# W005.net
KiCad netlist of a schematic drawn in EAGLE
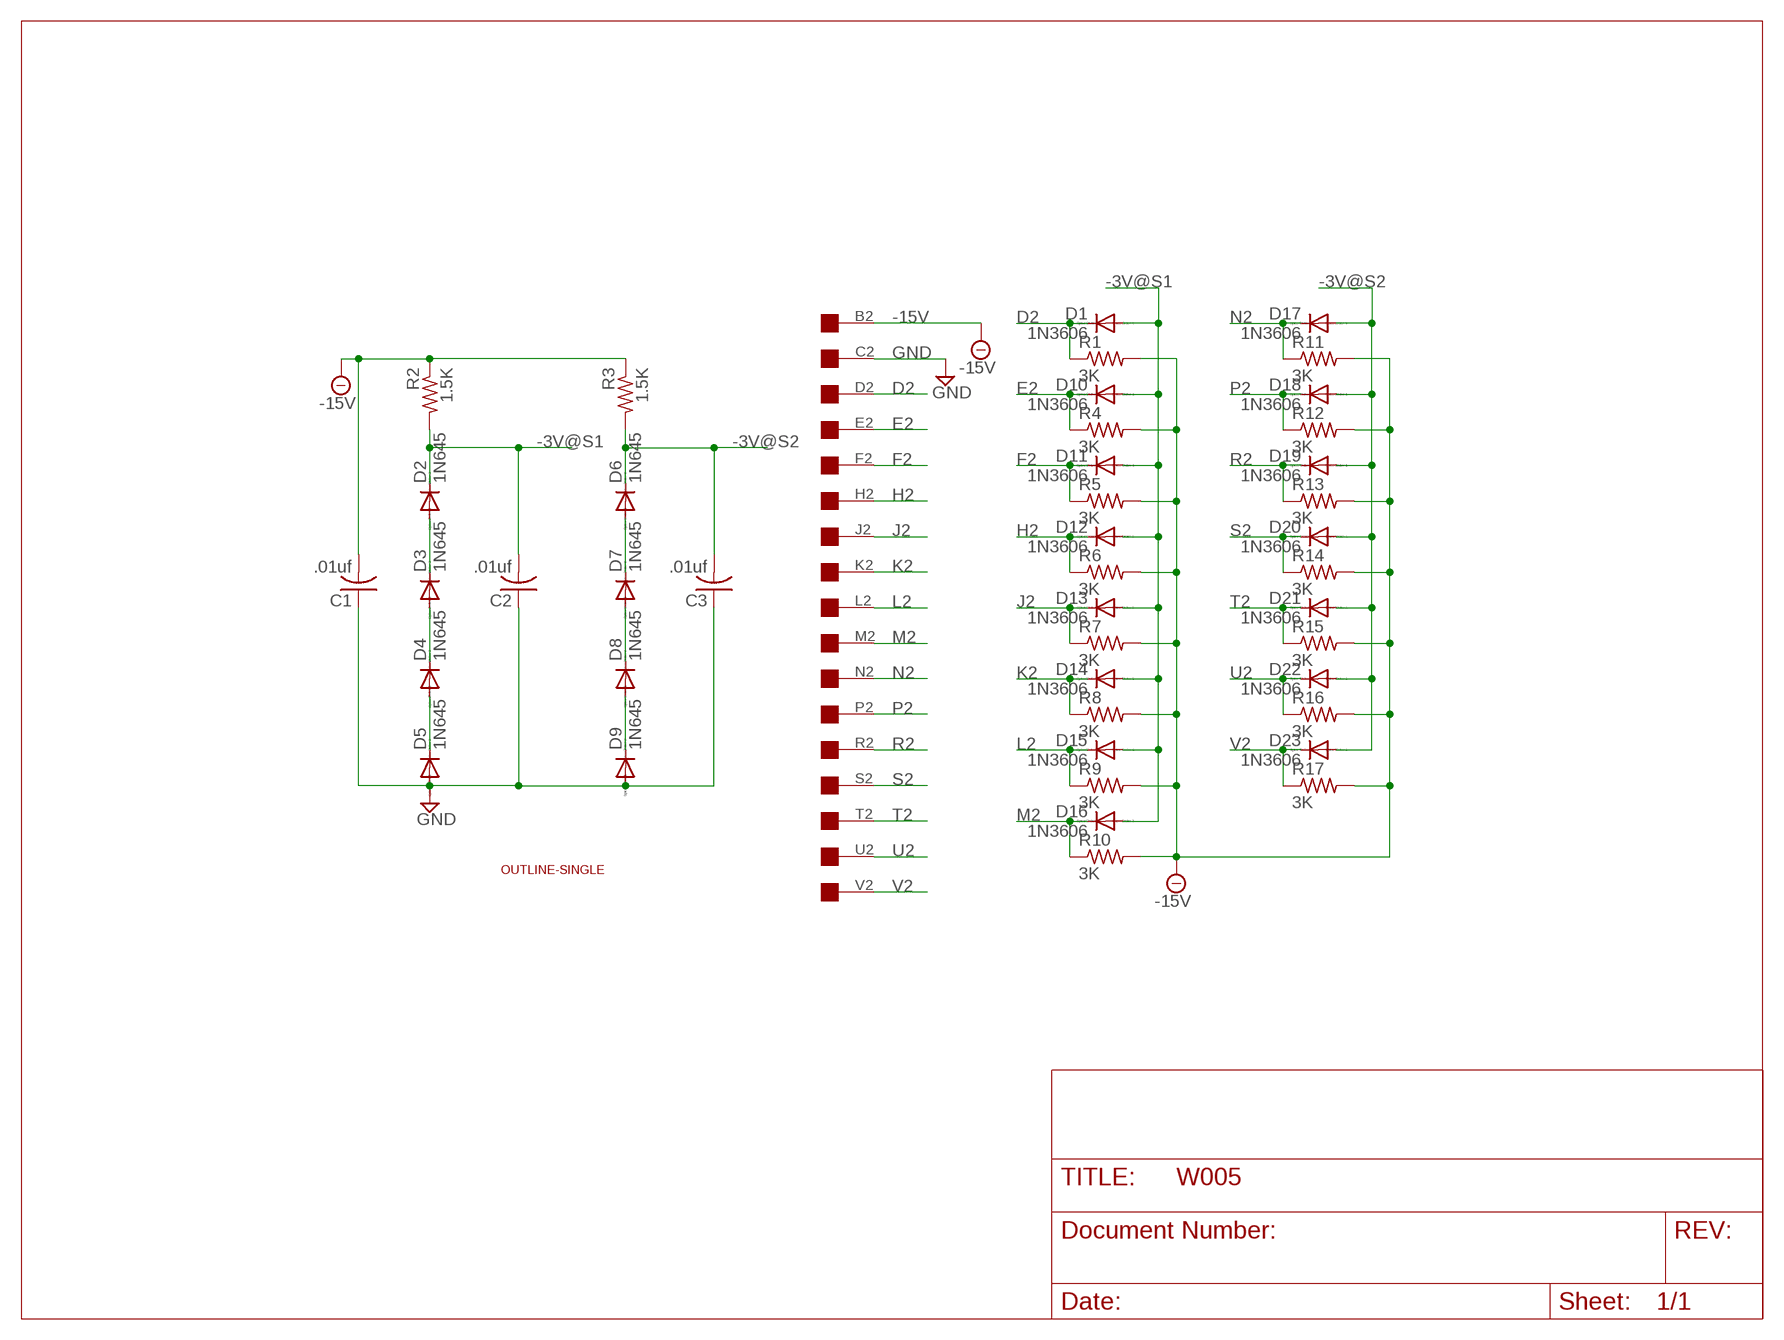
[diagram p0: schematic, sheet 1]

(export (version "E")
  (design (tool "Eeschema 10.0.6"))
  (components
    (comp (ref "C1")
      (value ".01uf")
      (footprint "eagle-import:C050-025X075")
      (libsource (lib "eagle-import") (part "C-US050-025X075"))
    )
    (comp (ref "C2")
      (value ".01uf")
      (footprint "eagle-import:C050-025X075")
      (libsource (lib "eagle-import") (part "C-US050-025X075"))
    )
    (comp (ref "C3")
      (value ".01uf")
      (footprint "eagle-import:C050-025X075")
      (libsource (lib "eagle-import") (part "C-US050-025X075"))
    )
    (comp (ref "D1")
      (value "1N3606")
      (footprint "eagle-import:DO35-10")
      (libsource (lib "eagle-import") (part "1N4148DO35-10"))
    )
    (comp (ref "D2")
      (value "1N645")
      (footprint "eagle-import:DO35-10")
      (libsource (lib "eagle-import") (part "1N4148DO35-10"))
    )
    (comp (ref "D3")
      (value "1N645")
      (footprint "eagle-import:DO35-10")
      (libsource (lib "eagle-import") (part "1N4148DO35-10"))
    )
    (comp (ref "D4")
      (value "1N645")
      (footprint "eagle-import:DO35-10")
      (libsource (lib "eagle-import") (part "1N4148DO35-10"))
    )
    (comp (ref "D5")
      (value "1N645")
      (footprint "eagle-import:DO35-10")
      (libsource (lib "eagle-import") (part "1N4148DO35-10"))
    )
    (comp (ref "D6")
      (value "1N645")
      (footprint "eagle-import:DO35-10")
      (libsource (lib "eagle-import") (part "1N4148DO35-10"))
    )
    (comp (ref "D7")
      (value "1N645")
      (footprint "eagle-import:DO35-10")
      (libsource (lib "eagle-import") (part "1N4148DO35-10"))
    )
    (comp (ref "D8")
      (value "1N645")
      (footprint "eagle-import:DO35-10")
      (libsource (lib "eagle-import") (part "1N4148DO35-10"))
    )
    (comp (ref "D9")
      (value "1N645")
      (footprint "eagle-import:DO35-10")
      (libsource (lib "eagle-import") (part "1N4148DO35-10"))
    )
    (comp (ref "D10")
      (value "1N3606")
      (footprint "eagle-import:DO35-10")
      (libsource (lib "eagle-import") (part "1N4148DO35-10"))
    )
    (comp (ref "D11")
      (value "1N3606")
      (footprint "eagle-import:DO35-10")
      (libsource (lib "eagle-import") (part "1N4148DO35-10"))
    )
    (comp (ref "D12")
      (value "1N3606")
      (footprint "eagle-import:DO35-10")
      (libsource (lib "eagle-import") (part "1N4148DO35-10"))
    )
    (comp (ref "D13")
      (value "1N3606")
      (footprint "eagle-import:DO35-10")
      (libsource (lib "eagle-import") (part "1N4148DO35-10"))
    )
    (comp (ref "D14")
      (value "1N3606")
      (footprint "eagle-import:DO35-10")
      (libsource (lib "eagle-import") (part "1N4148DO35-10"))
    )
    (comp (ref "D15")
      (value "1N3606")
      (footprint "eagle-import:DO35-10")
      (libsource (lib "eagle-import") (part "1N4148DO35-10"))
    )
    (comp (ref "D16")
      (value "1N3606")
      (footprint "eagle-import:DO35-10")
      (libsource (lib "eagle-import") (part "1N4148DO35-10"))
    )
    (comp (ref "D17")
      (value "1N3606")
      (footprint "eagle-import:DO35-10")
      (libsource (lib "eagle-import") (part "1N4148DO35-10"))
    )
    (comp (ref "D18")
      (value "1N3606")
      (footprint "eagle-import:DO35-10")
      (libsource (lib "eagle-import") (part "1N4148DO35-10"))
    )
    (comp (ref "D19")
      (value "1N3606")
      (footprint "eagle-import:DO35-10")
      (libsource (lib "eagle-import") (part "1N4148DO35-10"))
    )
    (comp (ref "D20")
      (value "1N3606")
      (footprint "eagle-import:DO35-10")
      (libsource (lib "eagle-import") (part "1N4148DO35-10"))
    )
    (comp (ref "D21")
      (value "1N3606")
      (footprint "eagle-import:DO35-10")
      (libsource (lib "eagle-import") (part "1N4148DO35-10"))
    )
    (comp (ref "D22")
      (value "1N3606")
      (footprint "eagle-import:DO35-10")
      (libsource (lib "eagle-import") (part "1N4148DO35-10"))
    )
    (comp (ref "D23")
      (value "1N3606")
      (footprint "eagle-import:DO35-10")
      (libsource (lib "eagle-import") (part "1N4148DO35-10"))
    )
    (comp (ref "R1")
      (value "3K")
      (footprint "eagle-import:0207_10")
      (libsource (lib "eagle-import") (part "R-US_0207/10"))
    )
    (comp (ref "R2")
      (value "1.5K")
      (footprint "eagle-import:0207_10")
      (libsource (lib "eagle-import") (part "R-US_0207/10"))
    )
    (comp (ref "R3")
      (value "1.5K")
      (footprint "eagle-import:0207_10")
      (libsource (lib "eagle-import") (part "R-US_0207/10"))
    )
    (comp (ref "R4")
      (value "3K")
      (footprint "eagle-import:0207_10")
      (libsource (lib "eagle-import") (part "R-US_0207/10"))
    )
    (comp (ref "R5")
      (value "3K")
      (footprint "eagle-import:0207_10")
      (libsource (lib "eagle-import") (part "R-US_0207/10"))
    )
    (comp (ref "R6")
      (value "3K")
      (footprint "eagle-import:0207_10")
      (libsource (lib "eagle-import") (part "R-US_0207/10"))
    )
    (comp (ref "R7")
      (value "3K")
      (footprint "eagle-import:0207_10")
      (libsource (lib "eagle-import") (part "R-US_0207/10"))
    )
    (comp (ref "R8")
      (value "3K")
      (footprint "eagle-import:0207_10")
      (libsource (lib "eagle-import") (part "R-US_0207/10"))
    )
    (comp (ref "R9")
      (value "3K")
      (footprint "eagle-import:0207_10")
      (libsource (lib "eagle-import") (part "R-US_0207/10"))
    )
    (comp (ref "R10")
      (value "3K")
      (footprint "eagle-import:0207_10")
      (libsource (lib "eagle-import") (part "R-US_0207/10"))
    )
    (comp (ref "R11")
      (value "3K")
      (footprint "eagle-import:0207_10")
      (libsource (lib "eagle-import") (part "R-US_0207/10"))
    )
    (comp (ref "R12")
      (value "3K")
      (footprint "eagle-import:0207_10")
      (libsource (lib "eagle-import") (part "R-US_0207/10"))
    )
    (comp (ref "R13")
      (value "3K")
      (footprint "eagle-import:0207_10")
      (libsource (lib "eagle-import") (part "R-US_0207/10"))
    )
    (comp (ref "R14")
      (value "3K")
      (footprint "eagle-import:0207_10")
      (libsource (lib "eagle-import") (part "R-US_0207/10"))
    )
    (comp (ref "R15")
      (value "3K")
      (footprint "eagle-import:0207_10")
      (libsource (lib "eagle-import") (part "R-US_0207/10"))
    )
    (comp (ref "R16")
      (value "3K")
      (footprint "eagle-import:0207_10")
      (libsource (lib "eagle-import") (part "R-US_0207/10"))
    )
    (comp (ref "R17")
      (value "3K")
      (footprint "eagle-import:0207_10")
      (libsource (lib "eagle-import") (part "R-US_0207/10"))
    )
    (comp (ref "U$1")
      (value "EDGE-1")
      (footprint "eagle-import:EDGE-CON1")
      (libsource (lib "eagle-import") (part "EDGE-1"))
    )
    (comp (ref "U$2")
      (value "OUTLINE-SINGLE")
      (footprint "eagle-import:SINGLE")
      (libsource (lib "eagle-import") (part "OUTLINE-SINGLE"))
    )
  )
  (nets
    (net (code "1") (name "-15V") (class "Default")
      (node (ref "C1") (pin "2") (pinfunction "2_2") (pintype "passive"))
      (node (ref "R1") (pin "2") (pinfunction "2_2") (pintype "passive"))
      (node (ref "R10") (pin "2") (pinfunction "2_2") (pintype "passive"))
      (node (ref "R11") (pin "2") (pinfunction "2_2") (pintype "passive"))
      (node (ref "R12") (pin "2") (pinfunction "2_2") (pintype "passive"))
      (node (ref "R13") (pin "2") (pinfunction "2_2") (pintype "passive"))
      (node (ref "R14") (pin "2") (pinfunction "2_2") (pintype "passive"))
      (node (ref "R15") (pin "2") (pinfunction "2_2") (pintype "passive"))
      (node (ref "R16") (pin "2") (pinfunction "2_2") (pintype "passive"))
      (node (ref "R17") (pin "2") (pinfunction "2_2") (pintype "passive"))
      (node (ref "R2") (pin "1") (pinfunction "1_1") (pintype "passive"))
      (node (ref "R3") (pin "1") (pinfunction "1_1") (pintype "passive"))
      (node (ref "R4") (pin "2") (pinfunction "2_2") (pintype "passive"))
      (node (ref "R5") (pin "2") (pinfunction "2_2") (pintype "passive"))
      (node (ref "R6") (pin "2") (pinfunction "2_2") (pintype "passive"))
      (node (ref "R7") (pin "2") (pinfunction "2_2") (pintype "passive"))
      (node (ref "R8") (pin "2") (pinfunction "2_2") (pintype "passive"))
      (node (ref "R9") (pin "2") (pinfunction "2_2") (pintype "passive"))
      (node (ref "U$1") (pin "B2") (pinfunction "1_B2") (pintype "bidirectional"))
    )
    (net (code "2") (name "/-3V@S1") (class "Default")
      (node (ref "C2") (pin "2") (pinfunction "2_2") (pintype "passive"))
      (node (ref "D1") (pin "A") (pinfunction "A_A") (pintype "passive"))
      (node (ref "D10") (pin "A") (pinfunction "A_A") (pintype "passive"))
      (node (ref "D11") (pin "A") (pinfunction "A_A") (pintype "passive"))
      (node (ref "D12") (pin "A") (pinfunction "A_A") (pintype "passive"))
      (node (ref "D13") (pin "A") (pinfunction "A_A") (pintype "passive"))
      (node (ref "D14") (pin "A") (pinfunction "A_A") (pintype "passive"))
      (node (ref "D15") (pin "A") (pinfunction "A_A") (pintype "passive"))
      (node (ref "D16") (pin "A") (pinfunction "A_A") (pintype "passive"))
      (node (ref "D2") (pin "C") (pinfunction "C_C") (pintype "passive"))
      (node (ref "R2") (pin "2") (pinfunction "2_2") (pintype "passive"))
    )
    (net (code "3") (name "/-3V@S2") (class "Default")
      (node (ref "C3") (pin "2") (pinfunction "2_2") (pintype "passive"))
      (node (ref "D17") (pin "A") (pinfunction "A_A") (pintype "passive"))
      (node (ref "D18") (pin "A") (pinfunction "A_A") (pintype "passive"))
      (node (ref "D19") (pin "A") (pinfunction "A_A") (pintype "passive"))
      (node (ref "D20") (pin "A") (pinfunction "A_A") (pintype "passive"))
      (node (ref "D21") (pin "A") (pinfunction "A_A") (pintype "passive"))
      (node (ref "D22") (pin "A") (pinfunction "A_A") (pintype "passive"))
      (node (ref "D23") (pin "A") (pinfunction "A_A") (pintype "passive"))
      (node (ref "D6") (pin "C") (pinfunction "C_C") (pintype "passive"))
      (node (ref "R3") (pin "2") (pinfunction "2_2") (pintype "passive"))
    )
    (net (code "4") (name "/D2") (class "Default")
      (node (ref "D1") (pin "C") (pinfunction "C_C") (pintype "passive"))
      (node (ref "R1") (pin "1") (pinfunction "1_1") (pintype "passive"))
      (node (ref "U$1") (pin "D2") (pinfunction "1_D2") (pintype "bidirectional"))
    )
    (net (code "5") (name "/E2") (class "Default")
      (node (ref "D10") (pin "C") (pinfunction "C_C") (pintype "passive"))
      (node (ref "R4") (pin "1") (pinfunction "1_1") (pintype "passive"))
      (node (ref "U$1") (pin "E2") (pinfunction "1_E2") (pintype "bidirectional"))
    )
    (net (code "6") (name "/F2") (class "Default")
      (node (ref "D11") (pin "C") (pinfunction "C_C") (pintype "passive"))
      (node (ref "R5") (pin "1") (pinfunction "1_1") (pintype "passive"))
      (node (ref "U$1") (pin "F2") (pinfunction "1_F2") (pintype "bidirectional"))
    )
    (net (code "7") (name "/H2") (class "Default")
      (node (ref "D12") (pin "C") (pinfunction "C_C") (pintype "passive"))
      (node (ref "R6") (pin "1") (pinfunction "1_1") (pintype "passive"))
      (node (ref "U$1") (pin "H2") (pinfunction "1_H2") (pintype "bidirectional"))
    )
    (net (code "8") (name "/J2") (class "Default")
      (node (ref "D13") (pin "C") (pinfunction "C_C") (pintype "passive"))
      (node (ref "R7") (pin "1") (pinfunction "1_1") (pintype "passive"))
      (node (ref "U$1") (pin "J2") (pinfunction "1_J2") (pintype "bidirectional"))
    )
    (net (code "9") (name "/K2") (class "Default")
      (node (ref "D14") (pin "C") (pinfunction "C_C") (pintype "passive"))
      (node (ref "R8") (pin "1") (pinfunction "1_1") (pintype "passive"))
      (node (ref "U$1") (pin "K2") (pinfunction "1_K2") (pintype "bidirectional"))
    )
    (net (code "10") (name "/L2") (class "Default")
      (node (ref "D15") (pin "C") (pinfunction "C_C") (pintype "passive"))
      (node (ref "R9") (pin "1") (pinfunction "1_1") (pintype "passive"))
      (node (ref "U$1") (pin "L2") (pinfunction "1_L2") (pintype "bidirectional"))
    )
    (net (code "11") (name "/M2") (class "Default")
      (node (ref "D16") (pin "C") (pinfunction "C_C") (pintype "passive"))
      (node (ref "R10") (pin "1") (pinfunction "1_1") (pintype "passive"))
      (node (ref "U$1") (pin "M2") (pinfunction "1_M2") (pintype "bidirectional"))
    )
    (net (code "12") (name "/N2") (class "Default")
      (node (ref "D17") (pin "C") (pinfunction "C_C") (pintype "passive"))
      (node (ref "R11") (pin "1") (pinfunction "1_1") (pintype "passive"))
      (node (ref "U$1") (pin "N2") (pinfunction "1_N2") (pintype "bidirectional"))
    )
    (net (code "13") (name "/P2") (class "Default")
      (node (ref "D18") (pin "C") (pinfunction "C_C") (pintype "passive"))
      (node (ref "R12") (pin "1") (pinfunction "1_1") (pintype "passive"))
      (node (ref "U$1") (pin "P2") (pinfunction "1_P2") (pintype "bidirectional"))
    )
    (net (code "14") (name "/R2") (class "Default")
      (node (ref "D19") (pin "C") (pinfunction "C_C") (pintype "passive"))
      (node (ref "R13") (pin "1") (pinfunction "1_1") (pintype "passive"))
      (node (ref "U$1") (pin "R2") (pinfunction "1_R2") (pintype "bidirectional"))
    )
    (net (code "15") (name "/S2") (class "Default")
      (node (ref "D20") (pin "C") (pinfunction "C_C") (pintype "passive"))
      (node (ref "R14") (pin "1") (pinfunction "1_1") (pintype "passive"))
      (node (ref "U$1") (pin "S2") (pinfunction "1_S2") (pintype "bidirectional"))
    )
    (net (code "16") (name "/T2") (class "Default")
      (node (ref "D21") (pin "C") (pinfunction "C_C") (pintype "passive"))
      (node (ref "R15") (pin "1") (pinfunction "1_1") (pintype "passive"))
      (node (ref "U$1") (pin "T2") (pinfunction "1_T2") (pintype "bidirectional"))
    )
    (net (code "17") (name "/U2") (class "Default")
      (node (ref "D22") (pin "C") (pinfunction "C_C") (pintype "passive"))
      (node (ref "R16") (pin "1") (pinfunction "1_1") (pintype "passive"))
      (node (ref "U$1") (pin "U2") (pinfunction "1_U2") (pintype "bidirectional"))
    )
    (net (code "18") (name "/V2") (class "Default")
      (node (ref "D23") (pin "C") (pinfunction "C_C") (pintype "passive"))
      (node (ref "R17") (pin "1") (pinfunction "1_1") (pintype "passive"))
      (node (ref "U$1") (pin "V2") (pinfunction "1_V2") (pintype "bidirectional"))
    )
    (net (code "19") (name "GND") (class "Default")
      (node (ref "C1") (pin "1") (pinfunction "1_1") (pintype "passive"))
      (node (ref "C2") (pin "1") (pinfunction "1_1") (pintype "passive"))
      (node (ref "C3") (pin "1") (pinfunction "1_1") (pintype "passive"))
      (node (ref "D5") (pin "A") (pinfunction "A_A") (pintype "passive"))
      (node (ref "D9") (pin "A") (pinfunction "A_A") (pintype "passive"))
      (node (ref "U$1") (pin "C2") (pinfunction "1_C2") (pintype "bidirectional"))
    )
    (net (code "20") (name "Net-(D2-PadA)") (class "Default")
      (node (ref "D2") (pin "A") (pinfunction "A_A") (pintype "passive"))
      (node (ref "D3") (pin "C") (pinfunction "C_C") (pintype "passive"))
    )
    (net (code "21") (name "Net-(D3-PadA)") (class "Default")
      (node (ref "D3") (pin "A") (pinfunction "A_A") (pintype "passive"))
      (node (ref "D4") (pin "C") (pinfunction "C_C") (pintype "passive"))
    )
    (net (code "22") (name "Net-(D4-PadA)") (class "Default")
      (node (ref "D4") (pin "A") (pinfunction "A_A") (pintype "passive"))
      (node (ref "D5") (pin "C") (pinfunction "C_C") (pintype "passive"))
    )
    (net (code "23") (name "Net-(D6-PadA)") (class "Default")
      (node (ref "D6") (pin "A") (pinfunction "A_A") (pintype "passive"))
      (node (ref "D7") (pin "C") (pinfunction "C_C") (pintype "passive"))
    )
    (net (code "24") (name "Net-(D7-PadA)") (class "Default")
      (node (ref "D7") (pin "A") (pinfunction "A_A") (pintype "passive"))
      (node (ref "D8") (pin "C") (pinfunction "C_C") (pintype "passive"))
    )
    (net (code "25") (name "Net-(D8-PadA)") (class "Default")
      (node (ref "D8") (pin "A") (pinfunction "A_A") (pintype "passive"))
      (node (ref "D9") (pin "C") (pinfunction "C_C") (pintype "passive"))
    )
  )
)
